# ModuloWIFI.net
KiCad netlist of a schematic drawn in Altium Designer
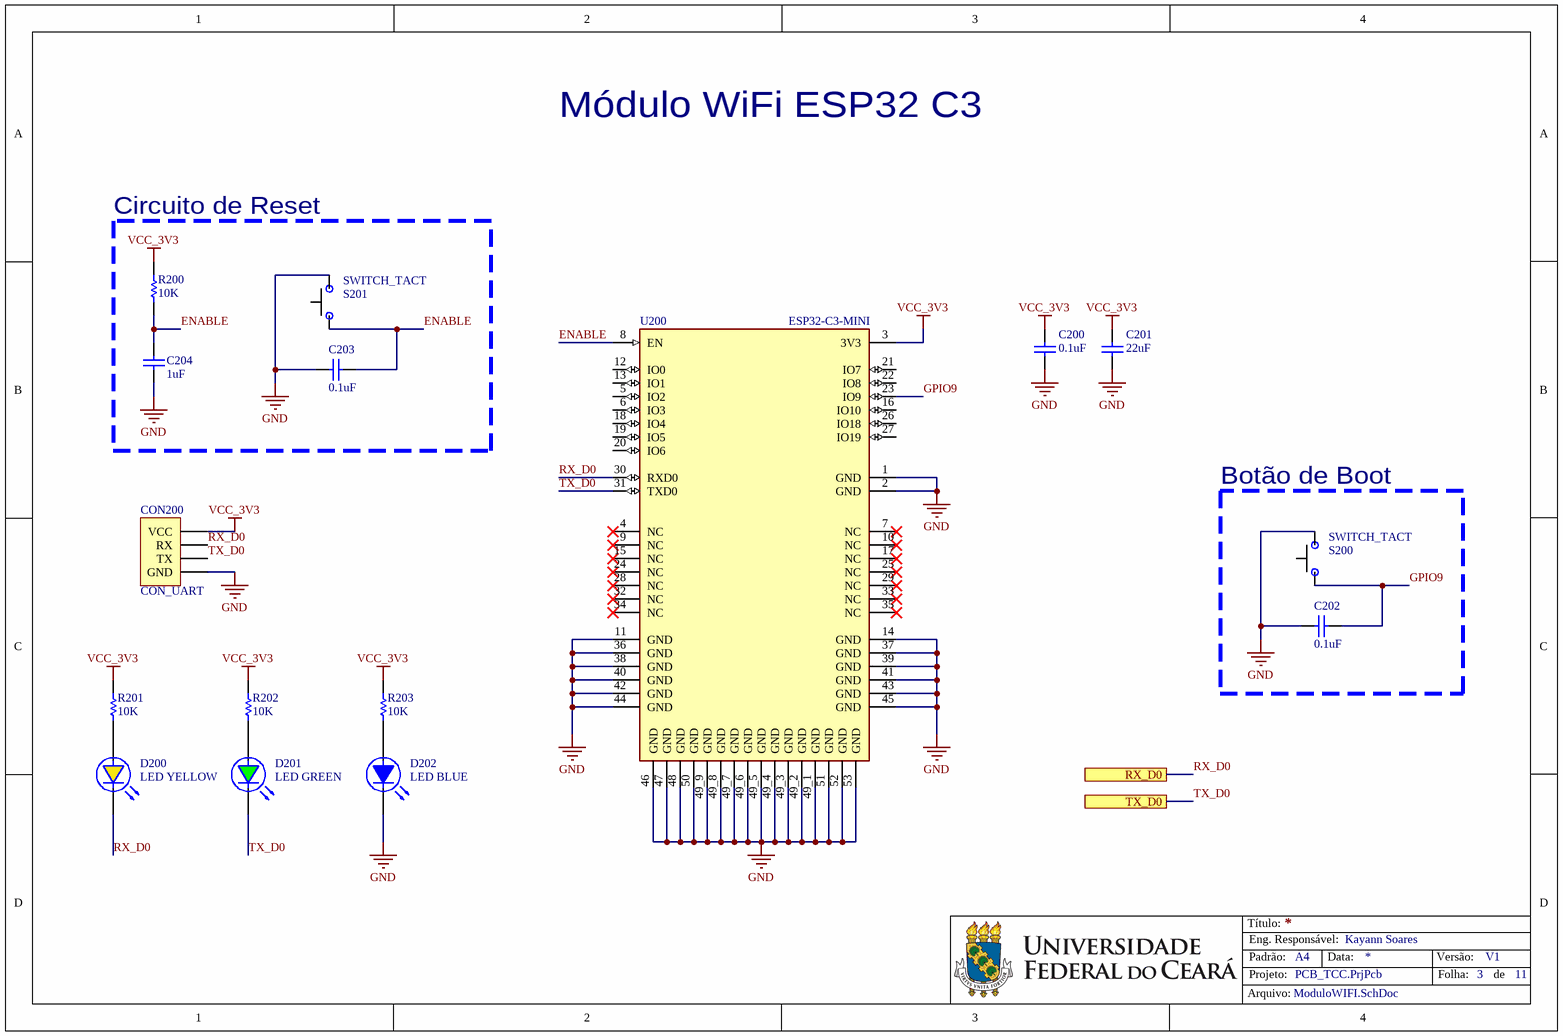
[diagram p0: ModuloWIFI.SchDoc]

(export (version "E")
  (design (tool "Eeschema 10.0.6"))
  (components
    (comp (ref "C200")
      (value "0.1uF")
      (footprint "CAP_CER_0603")
      (libsource (lib "PCB_TCC") (part "CAP_CER_0.1uF_0603"))
    )
    (comp (ref "C201")
      (value "22uF")
      (footprint "CAP_CER_0603")
      (libsource (lib "PCB_TCC") (part "CAP_CER_22uF_0603"))
    )
    (comp (ref "C202")
      (value "0.1uF")
      (footprint "CAP_CER_0603")
      (libsource (lib "PCB_TCC") (part "CAP_CER_0.1uF_0603"))
    )
    (comp (ref "C203")
      (value "0.1uF")
      (footprint "CAP_CER_0603")
      (libsource (lib "PCB_TCC") (part "CAP_CER_0.1uF_0603"))
    )
    (comp (ref "C204")
      (value "1uF")
      (footprint "CAP_CER_0603")
      (libsource (lib "PCB_TCC") (part "CAP_CER_1uF_0603"))
    )
    (comp (ref "CON200")
      (value "CON_UART")
      (footprint "CON_UART")
      (libsource (lib "PCB_TCC") (part "CON_UART"))
    )
    (comp (ref "D200")
      (value "LED YELLOW")
      (footprint "LED_YELLOW_SMD_0603")
      (libsource (lib "PCB_TCC") (part "LED_YELLOW_SMD_0603"))
    )
    (comp (ref "D201")
      (value "LED GREEN")
      (footprint "LED_GREEN_SMD_0603")
      (libsource (lib "PCB_TCC") (part "LED_GREEN_SMD_0603"))
    )
    (comp (ref "D202")
      (value "LED BLUE")
      (footprint "LED_BLUE_SMD_0603")
      (libsource (lib "PCB_TCC") (part "LED_BLUE_SMD_0603"))
    )
    (comp (ref "R200") (value "10K") (footprint "RES_0603") (libsource (lib "PCB_TCC") (part "RES_10K_0603")))
    (comp (ref "R201") (value "10K") (footprint "RES_0603") (libsource (lib "PCB_TCC") (part "RES_10K_0603")))
    (comp (ref "R202") (value "10K") (footprint "RES_0603") (libsource (lib "PCB_TCC") (part "RES_10K_0603")))
    (comp (ref "R203") (value "10K") (footprint "RES_0603") (libsource (lib "PCB_TCC") (part "RES_10K_0603")))
    (comp (ref "S200")
      (value "SWITCH_TACT")
      (footprint "SWITCH_TACT_6.0x3.5")
      (libsource (lib "PCB_TCC") (part "SWITCH_TACT_6.0x3.5"))
    )
    (comp (ref "S201")
      (value "SWITCH_TACT")
      (footprint "SWITCH_TACT_6.0x3.5")
      (libsource (lib "PCB_TCC") (part "SWITCH_TACT_6.0x3.5"))
    )
    (comp (ref "U200")
      (value "ESP32-C3-MINI")
      (footprint "ESP32-C3-MINI")
      (libsource (lib "PCB_TCC") (part "ESP32-C3-MINI"))
    )
  )
  (nets
    (net (code "1") (name "/ENABLE") (class "Default")
      (node (ref "C203") (pin "2") (pinfunction "2_2") (pintype "passive"))
      (node (ref "C204") (pin "2") (pinfunction "2_2") (pintype "passive"))
      (node (ref "R200") (pin "1") (pinfunction "1_1") (pintype "passive"))
      (node (ref "S201") (pin "2") (pinfunction "2_2") (pintype "passive"))
      (node (ref "U200") (pin "8") (pinfunction "EN_8") (pintype "input"))
    )
    (net (code "2") (name "/GPIO9") (class "Default")
      (node (ref "C202") (pin "2") (pinfunction "2_2") (pintype "passive"))
      (node (ref "S200") (pin "2") (pinfunction "2_2") (pintype "passive"))
      (node (ref "U200") (pin "23") (pinfunction "IO9_23") (pintype "bidirectional"))
    )
    (net (code "3") (name "/RX_D0") (class "Default")
      (node (ref "CON200") (pin "2") (pinfunction "RX_2") (pintype "passive"))
      (node (ref "D200") (pin "K") (pinfunction "K_K") (pintype "passive"))
      (node (ref "U200") (pin "30") (pinfunction "RXD0_30") (pintype "bidirectional"))
    )
    (net (code "4") (name "/TX_D0") (class "Default")
      (node (ref "CON200") (pin "3") (pinfunction "TX_3") (pintype "passive"))
      (node (ref "D201") (pin "K") (pinfunction "K_K") (pintype "passive"))
      (node (ref "U200") (pin "31") (pinfunction "TXD0_31") (pintype "bidirectional"))
    )
    (net (code "5") (name "GND") (class "Default")
      (node (ref "C200") (pin "1") (pinfunction "1_1") (pintype "passive"))
      (node (ref "C201") (pin "1") (pinfunction "1_1") (pintype "passive"))
      (node (ref "C202") (pin "1") (pinfunction "1_1") (pintype "passive"))
      (node (ref "C203") (pin "1") (pinfunction "1_1") (pintype "passive"))
      (node (ref "C204") (pin "1") (pinfunction "1_1") (pintype "passive"))
      (node (ref "CON200") (pin "4") (pinfunction "GND_4") (pintype "passive"))
      (node (ref "D202") (pin "K") (pinfunction "K_K") (pintype "passive"))
      (node (ref "S200") (pin "1") (pinfunction "1_1") (pintype "passive"))
      (node (ref "S201") (pin "1") (pinfunction "1_1") (pintype "passive"))
      (node (ref "U200") (pin "1") (pinfunction "GND_1") (pintype "power_in"))
      (node (ref "U200") (pin "11") (pinfunction "GND_11") (pintype "power_in"))
      (node (ref "U200") (pin "14") (pinfunction "GND_14") (pintype "power_in"))
      (node (ref "U200") (pin "2") (pinfunction "GND_2") (pintype "power_in"))
      (node (ref "U200") (pin "36") (pinfunction "GND_36") (pintype "power_in"))
      (node (ref "U200") (pin "37") (pinfunction "GND_37") (pintype "power_in"))
      (node (ref "U200") (pin "38") (pinfunction "GND_38") (pintype "power_in"))
      (node (ref "U200") (pin "39") (pinfunction "GND_39") (pintype "power_in"))
      (node (ref "U200") (pin "40") (pinfunction "GND_40") (pintype "power_in"))
      (node (ref "U200") (pin "41") (pinfunction "GND_41") (pintype "power_in"))
      (node (ref "U200") (pin "42") (pinfunction "GND_42") (pintype "power_in"))
      (node (ref "U200") (pin "43") (pinfunction "GND_43") (pintype "power_in"))
      (node (ref "U200") (pin "44") (pinfunction "GND_44") (pintype "power_in"))
      (node (ref "U200") (pin "45") (pinfunction "GND_45") (pintype "power_in"))
      (node (ref "U200") (pin "46") (pinfunction "GND_46") (pintype "power_in"))
      (node (ref "U200") (pin "47") (pinfunction "GND_47") (pintype "power_in"))
      (node (ref "U200") (pin "48") (pinfunction "GND_48") (pintype "power_in"))
      (node (ref "U200") (pin "49_1") (pinfunction "GND_49_1") (pintype "power_in"))
      (node (ref "U200") (pin "49_2") (pinfunction "GND_49_2") (pintype "power_in"))
      (node (ref "U200") (pin "49_3") (pinfunction "GND_49_3") (pintype "power_in"))
      (node (ref "U200") (pin "49_4") (pinfunction "GND_49_4") (pintype "power_in"))
      (node (ref "U200") (pin "49_5") (pinfunction "GND_49_5") (pintype "power_in"))
      (node (ref "U200") (pin "49_6") (pinfunction "GND_49_6") (pintype "power_in"))
      (node (ref "U200") (pin "49_7") (pinfunction "GND_49_7") (pintype "power_in"))
      (node (ref "U200") (pin "49_8") (pinfunction "GND_49_8") (pintype "power_in"))
      (node (ref "U200") (pin "49_9") (pinfunction "GND_49_9") (pintype "power_in"))
      (node (ref "U200") (pin "50") (pinfunction "GND_50") (pintype "power_in"))
      (node (ref "U200") (pin "51") (pinfunction "GND_51") (pintype "power_in"))
      (node (ref "U200") (pin "52") (pinfunction "GND_52") (pintype "power_in"))
      (node (ref "U200") (pin "53") (pinfunction "GND_53") (pintype "power_in"))
    )
    (net (code "6") (name "Net-(D200-PadA)") (class "Default")
      (node (ref "D200") (pin "A") (pinfunction "A_A") (pintype "passive"))
      (node (ref "R201") (pin "1") (pinfunction "1_1") (pintype "passive"))
    )
    (net (code "7") (name "Net-(D201-PadA)") (class "Default")
      (node (ref "D201") (pin "A") (pinfunction "A_A") (pintype "passive"))
      (node (ref "R202") (pin "1") (pinfunction "1_1") (pintype "passive"))
    )
    (net (code "8") (name "Net-(D202-PadA)") (class "Default")
      (node (ref "D202") (pin "A") (pinfunction "A_A") (pintype "passive"))
      (node (ref "R203") (pin "1") (pinfunction "1_1") (pintype "passive"))
    )
    (net (code "9") (name "VCC_3V3") (class "Default")
      (node (ref "C200") (pin "2") (pinfunction "2_2") (pintype "passive"))
      (node (ref "C201") (pin "2") (pinfunction "2_2") (pintype "passive"))
      (node (ref "CON200") (pin "1") (pinfunction "VCC_1") (pintype "passive"))
      (node (ref "R200") (pin "2") (pinfunction "2_2") (pintype "passive"))
      (node (ref "R201") (pin "2") (pinfunction "2_2") (pintype "passive"))
      (node (ref "R202") (pin "2") (pinfunction "2_2") (pintype "passive"))
      (node (ref "R203") (pin "2") (pinfunction "2_2") (pintype "passive"))
      (node (ref "U200") (pin "3") (pinfunction "3V3_3") (pintype "power_in"))
    )
    (net (code "10") (name "unconnected-(U200-IO0-Pad12)") (class "Default")
      (node (ref "U200") (pin "12") (pinfunction "IO0_12") (pintype "bidirectional"))
    )
    (net (code "11") (name "unconnected-(U200-IO1-Pad13)") (class "Default")
      (node (ref "U200") (pin "13") (pinfunction "IO1_13") (pintype "bidirectional"))
    )
    (net (code "12") (name "unconnected-(U200-IO2-Pad5)") (class "Default")
      (node (ref "U200") (pin "5") (pinfunction "IO2_5") (pintype "bidirectional"))
    )
    (net (code "13") (name "unconnected-(U200-IO3-Pad6)") (class "Default")
      (node (ref "U200") (pin "6") (pinfunction "IO3_6") (pintype "bidirectional"))
    )
    (net (code "14") (name "unconnected-(U200-IO4-Pad18)") (class "Default")
      (node (ref "U200") (pin "18") (pinfunction "IO4_18") (pintype "bidirectional"))
    )
    (net (code "15") (name "unconnected-(U200-IO5-Pad19)") (class "Default")
      (node (ref "U200") (pin "19") (pinfunction "IO5_19") (pintype "bidirectional"))
    )
    (net (code "16") (name "unconnected-(U200-IO6-Pad20)") (class "Default")
      (node (ref "U200") (pin "20") (pinfunction "IO6_20") (pintype "bidirectional"))
    )
    (net (code "17") (name "unconnected-(U200-IO7-Pad21)") (class "Default")
      (node (ref "U200") (pin "21") (pinfunction "IO7_21") (pintype "bidirectional"))
    )
    (net (code "18") (name "unconnected-(U200-IO8-Pad22)") (class "Default")
      (node (ref "U200") (pin "22") (pinfunction "IO8_22") (pintype "bidirectional"))
    )
    (net (code "19") (name "unconnected-(U200-IO10-Pad16)") (class "Default")
      (node (ref "U200") (pin "16") (pinfunction "IO10_16") (pintype "bidirectional"))
    )
    (net (code "20") (name "unconnected-(U200-IO18-Pad26)") (class "Default")
      (node (ref "U200") (pin "26") (pinfunction "IO18_26") (pintype "bidirectional"))
    )
    (net (code "21") (name "unconnected-(U200-IO19-Pad27)") (class "Default")
      (node (ref "U200") (pin "27") (pinfunction "IO19_27") (pintype "bidirectional"))
    )
    (net (code "22") (name "unconnected-(U200-NC-Pad4)") (class "Default")
      (node (ref "U200") (pin "4") (pinfunction "NC_4") (pintype "passive+no_connect"))
    )
    (net (code "23") (name "unconnected-(U200-NC-Pad7)") (class "Default")
      (node (ref "U200") (pin "7") (pinfunction "NC_7") (pintype "passive+no_connect"))
    )
    (net (code "24") (name "unconnected-(U200-NC-Pad9)") (class "Default")
      (node (ref "U200") (pin "9") (pinfunction "NC_9") (pintype "passive+no_connect"))
    )
    (net (code "25") (name "unconnected-(U200-NC-Pad10)") (class "Default")
      (node (ref "U200") (pin "10") (pinfunction "NC_10") (pintype "passive+no_connect"))
    )
    (net (code "26") (name "unconnected-(U200-NC-Pad15)") (class "Default")
      (node (ref "U200") (pin "15") (pinfunction "NC_15") (pintype "passive+no_connect"))
    )
    (net (code "27") (name "unconnected-(U200-NC-Pad17)") (class "Default")
      (node (ref "U200") (pin "17") (pinfunction "NC_17") (pintype "passive+no_connect"))
    )
    (net (code "28") (name "unconnected-(U200-NC-Pad24)") (class "Default")
      (node (ref "U200") (pin "24") (pinfunction "NC_24") (pintype "passive+no_connect"))
    )
    (net (code "29") (name "unconnected-(U200-NC-Pad25)") (class "Default")
      (node (ref "U200") (pin "25") (pinfunction "NC_25") (pintype "passive+no_connect"))
    )
    (net (code "30") (name "unconnected-(U200-NC-Pad28)") (class "Default")
      (node (ref "U200") (pin "28") (pinfunction "NC_28") (pintype "passive+no_connect"))
    )
    (net (code "31") (name "unconnected-(U200-NC-Pad29)") (class "Default")
      (node (ref "U200") (pin "29") (pinfunction "NC_29") (pintype "passive+no_connect"))
    )
    (net (code "32") (name "unconnected-(U200-NC-Pad32)") (class "Default")
      (node (ref "U200") (pin "32") (pinfunction "NC_32") (pintype "passive+no_connect"))
    )
    (net (code "33") (name "unconnected-(U200-NC-Pad33)") (class "Default")
      (node (ref "U200") (pin "33") (pinfunction "NC_33") (pintype "passive+no_connect"))
    )
    (net (code "34") (name "unconnected-(U200-NC-Pad34)") (class "Default")
      (node (ref "U200") (pin "34") (pinfunction "NC_34") (pintype "passive+no_connect"))
    )
    (net (code "35") (name "unconnected-(U200-NC-Pad35)") (class "Default")
      (node (ref "U200") (pin "35") (pinfunction "NC_35") (pintype "passive+no_connect"))
    )
  )
)
